# Beta24_to71.net
KiCad netlist of a schematic drawn in EAGLE
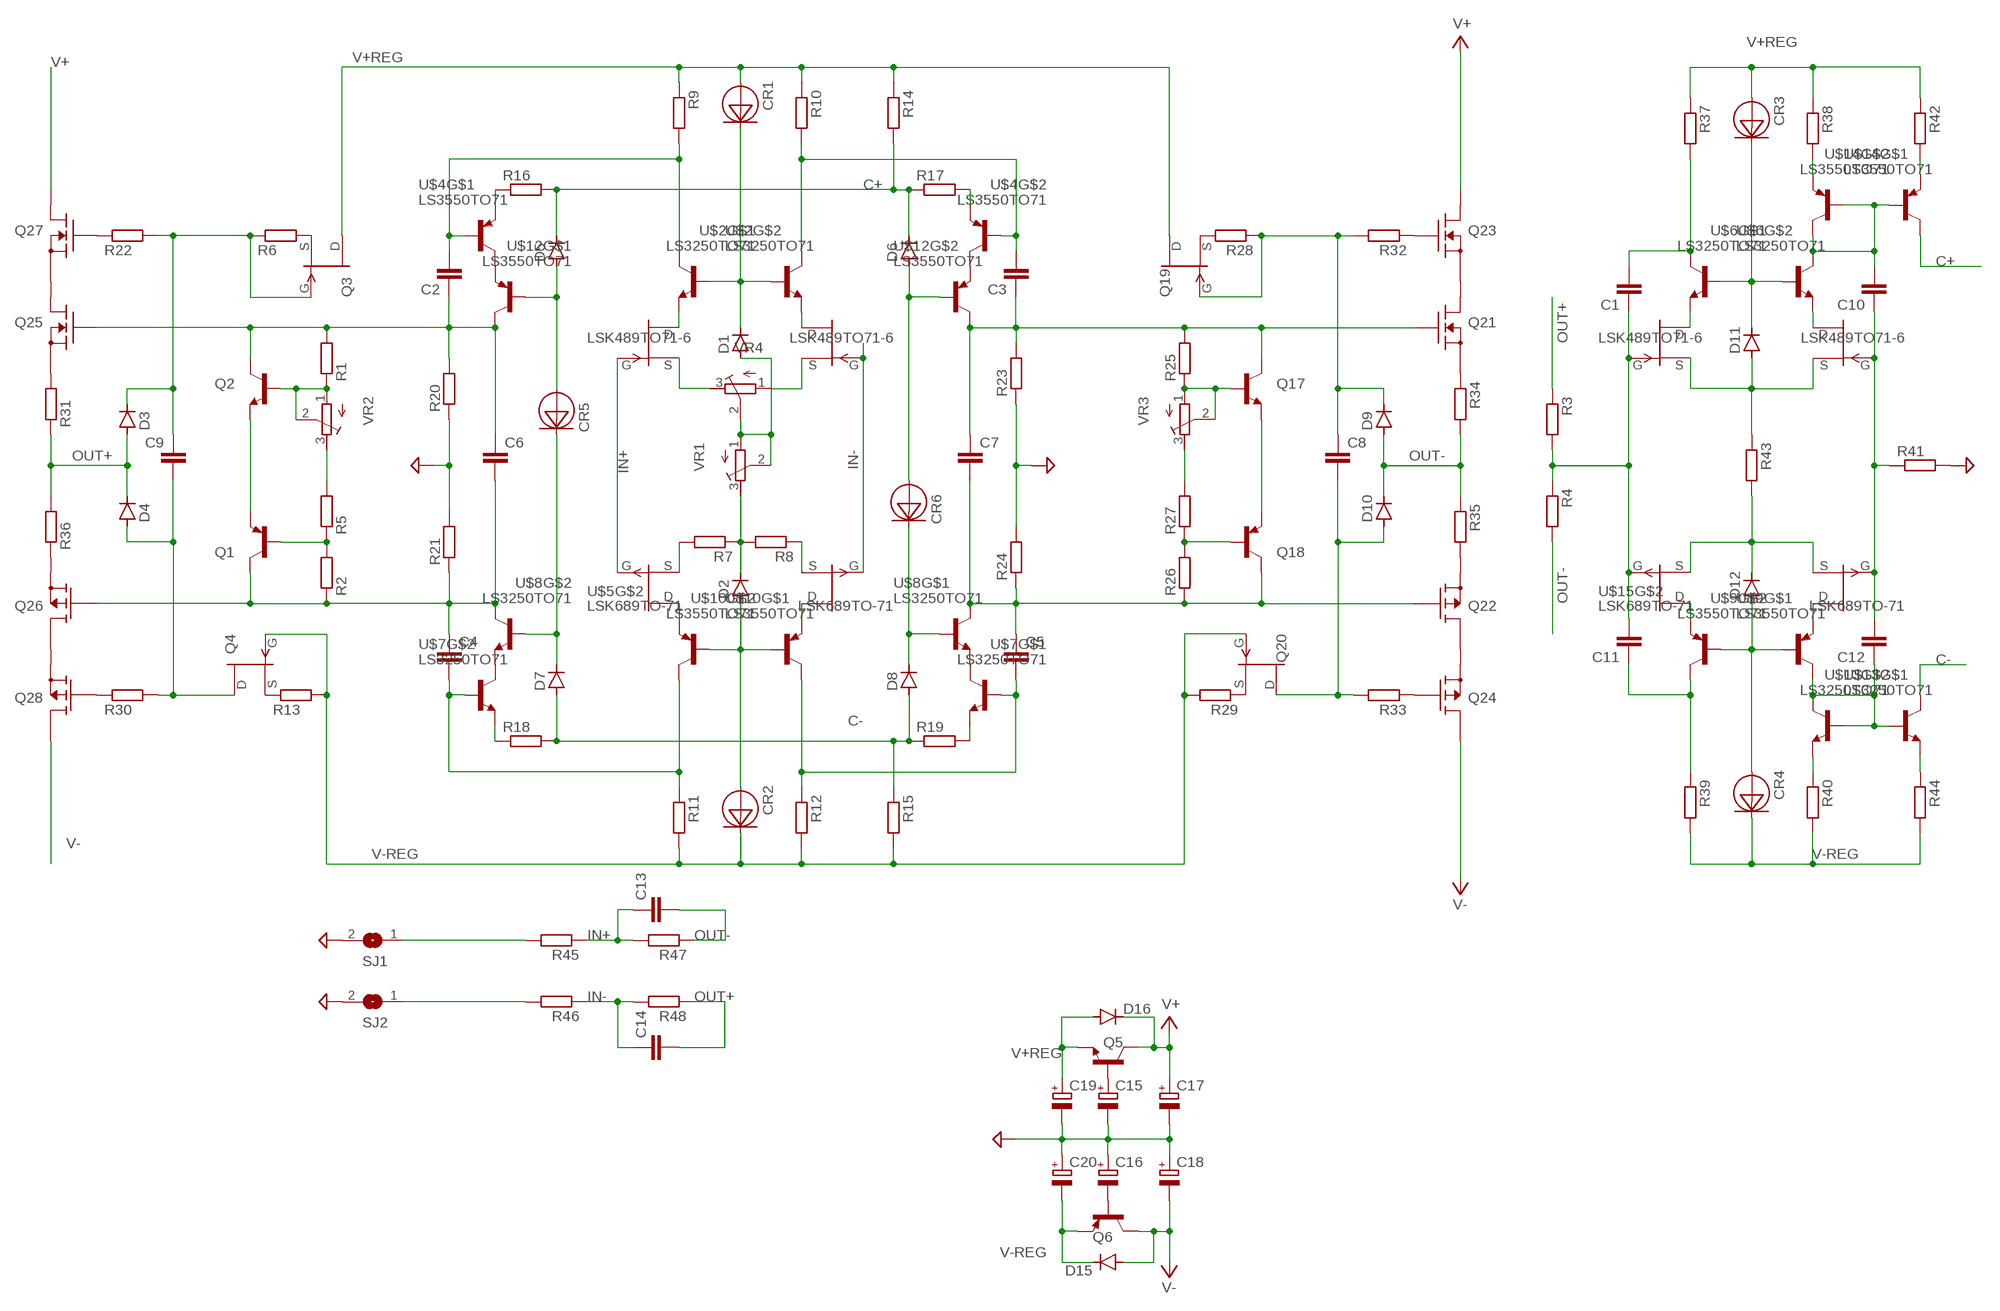
[diagram p0: schematic, sheet 1]

(export (version "E")
  (design (tool "Eeschema 10.0.6"))
  (components
    (comp (ref "C1")
      (value "C-EUC1206")
      (footprint "eagle-import:C1206")
      (libsource (lib "eagle-import") (part "C-EUC1206"))
    )
    (comp (ref "C2")
      (value "C-EUC1206")
      (footprint "eagle-import:C1206")
      (libsource (lib "eagle-import") (part "C-EUC1206"))
    )
    (comp (ref "C3")
      (value "C-EUC1206")
      (footprint "eagle-import:C1206")
      (libsource (lib "eagle-import") (part "C-EUC1206"))
    )
    (comp (ref "C4")
      (value "C-EUC1206")
      (footprint "eagle-import:C1206")
      (libsource (lib "eagle-import") (part "C-EUC1206"))
    )
    (comp (ref "C5")
      (value "C-EUC1206")
      (footprint "eagle-import:C1206")
      (libsource (lib "eagle-import") (part "C-EUC1206"))
    )
    (comp (ref "C6")
      (value "C-EUC1206")
      (footprint "eagle-import:C1206")
      (libsource (lib "eagle-import") (part "C-EUC1206"))
    )
    (comp (ref "C7")
      (value "C-EUC1206")
      (footprint "eagle-import:C1206")
      (libsource (lib "eagle-import") (part "C-EUC1206"))
    )
    (comp (ref "C8")
      (value "C-EUC1206")
      (footprint "eagle-import:C1206")
      (libsource (lib "eagle-import") (part "C-EUC1206"))
    )
    (comp (ref "C9")
      (value "C-EUC1206")
      (footprint "eagle-import:C1206")
      (libsource (lib "eagle-import") (part "C-EUC1206"))
    )
    (comp (ref "C10")
      (value "C-EUC1206")
      (footprint "eagle-import:C1206")
      (libsource (lib "eagle-import") (part "C-EUC1206"))
    )
    (comp (ref "C11")
      (value "C-EUC1206")
      (footprint "eagle-import:C1206")
      (libsource (lib "eagle-import") (part "C-EUC1206"))
    )
    (comp (ref "C12")
      (value "C-EUC1206")
      (footprint "eagle-import:C1206")
      (libsource (lib "eagle-import") (part "C-EUC1206"))
    )
    (comp (ref "C13")
      (value "C-EUC1206")
      (footprint "eagle-import:C1206")
      (libsource (lib "eagle-import") (part "C-EUC1206"))
    )
    (comp (ref "C14")
      (value "C-EUC1206")
      (footprint "eagle-import:C1206")
      (libsource (lib "eagle-import") (part "C-EUC1206"))
    )
    (comp (ref "C15")
      (value "CPOL-EUE5-13")
      (footprint "eagle-import:E5-13")
      (libsource (lib "eagle-import") (part "CPOL-EUE5-13"))
    )
    (comp (ref "C16")
      (value "CPOL-EUE5-13")
      (footprint "eagle-import:E5-13")
      (libsource (lib "eagle-import") (part "CPOL-EUE5-13"))
    )
    (comp (ref "C17")
      (value "CPOL-EUE7.5-18")
      (footprint "eagle-import:E7,5-18")
      (libsource (lib "eagle-import") (part "CPOL-EUE7.5-18"))
    )
    (comp (ref "C18")
      (value "CPOL-EUE7.5-18")
      (footprint "eagle-import:E7,5-18")
      (libsource (lib "eagle-import") (part "CPOL-EUE7.5-18"))
    )
    (comp (ref "C19")
      (value "CPOL-EUE5-13")
      (footprint "eagle-import:E5-13")
      (libsource (lib "eagle-import") (part "CPOL-EUE5-13"))
    )
    (comp (ref "C20")
      (value "CPOL-EUE5-13")
      (footprint "eagle-import:E5-13")
      (libsource (lib "eagle-import") (part "CPOL-EUE5-13"))
    )
    (comp (ref "CR1")
      (value "1N5283")
      (footprint "eagle-import:SMD")
      (libsource (lib "eagle-import") (part "1N5283"))
    )
    (comp (ref "CR2")
      (value "1N5283")
      (footprint "eagle-import:SMD")
      (libsource (lib "eagle-import") (part "1N5283"))
    )
    (comp (ref "CR3")
      (value "1N5283")
      (footprint "eagle-import:SMD")
      (libsource (lib "eagle-import") (part "1N5283"))
    )
    (comp (ref "CR4")
      (value "1N5283")
      (footprint "eagle-import:SMD")
      (libsource (lib "eagle-import") (part "1N5283"))
    )
    (comp (ref "CR5")
      (value "1N5283")
      (footprint "eagle-import:SMD")
      (libsource (lib "eagle-import") (part "1N5283"))
    )
    (comp (ref "CR6")
      (value "1N5283")
      (footprint "eagle-import:SMD")
      (libsource (lib "eagle-import") (part "1N5283"))
    )
    (comp (ref "D1")
      (value "DIODE-SOD80C")
      (footprint "eagle-import:SOD80C")
      (libsource (lib "eagle-import") (part "DIODE-SOD80C"))
    )
    (comp (ref "D2")
      (value "DIODE-SOD80C")
      (footprint "eagle-import:SOD80C")
      (libsource (lib "eagle-import") (part "DIODE-SOD80C"))
    )
    (comp (ref "D3")
      (value "DIODE-SOD80C")
      (footprint "eagle-import:SOD80C")
      (libsource (lib "eagle-import") (part "DIODE-SOD80C"))
    )
    (comp (ref "D4")
      (value "DIODE-SOD80C")
      (footprint "eagle-import:SOD80C")
      (libsource (lib "eagle-import") (part "DIODE-SOD80C"))
    )
    (comp (ref "D5")
      (value "DIODE-SOD80C")
      (footprint "eagle-import:SOD80C")
      (libsource (lib "eagle-import") (part "DIODE-SOD80C"))
    )
    (comp (ref "D6")
      (value "DIODE-SOD80C")
      (footprint "eagle-import:SOD80C")
      (libsource (lib "eagle-import") (part "DIODE-SOD80C"))
    )
    (comp (ref "D7")
      (value "DIODE-SOD80C")
      (footprint "eagle-import:SOD80C")
      (libsource (lib "eagle-import") (part "DIODE-SOD80C"))
    )
    (comp (ref "D8")
      (value "DIODE-SOD80C")
      (footprint "eagle-import:SOD80C")
      (libsource (lib "eagle-import") (part "DIODE-SOD80C"))
    )
    (comp (ref "D9")
      (value "DIODE-SOD80C")
      (footprint "eagle-import:SOD80C")
      (libsource (lib "eagle-import") (part "DIODE-SOD80C"))
    )
    (comp (ref "D10")
      (value "DIODE-SOD80C")
      (footprint "eagle-import:SOD80C")
      (libsource (lib "eagle-import") (part "DIODE-SOD80C"))
    )
    (comp (ref "D11")
      (value "DIODE-SOD80C")
      (footprint "eagle-import:SOD80C")
      (libsource (lib "eagle-import") (part "DIODE-SOD80C"))
    )
    (comp (ref "D12")
      (value "DIODE-SOD80C")
      (footprint "eagle-import:SOD80C")
      (libsource (lib "eagle-import") (part "DIODE-SOD80C"))
    )
    (comp (ref "D15")
      (value "DIODE-SMB")
      (footprint "eagle-import:SMB")
      (libsource (lib "eagle-import") (part "DIODE-SMB"))
    )
    (comp (ref "D16")
      (value "DIODE-SMB")
      (footprint "eagle-import:SMB")
      (libsource (lib "eagle-import") (part "DIODE-SMB"))
    )
    (comp (ref "Q1")
      (value "TRANSISTOR_BC858C-PNP-SOT23-BEC")
      (footprint "eagle-import:TRANSISTOR_SOT23-BEC")
      (libsource (lib "eagle-import") (part "TRANSISTOR_-PNP-SOT23-BECBC858C"))
    )
    (comp (ref "Q2")
      (value "TRANSISTOR_BC850-NPN-SOT23-BEC")
      (footprint "eagle-import:TRANSISTOR_SOT23-BEC")
      (libsource (lib "eagle-import") (part "TRANSISTOR_-NPN-SOT23-BECBC850"))
    )
    (comp (ref "Q3")
      (value "2N4392")
      (footprint "eagle-import:TO18")
      (libsource (lib "eagle-import") (part "2N4392"))
    )
    (comp (ref "Q4")
      (value "2N4392")
      (footprint "eagle-import:TO18")
      (libsource (lib "eagle-import") (part "2N4392"))
    )
    (comp (ref "Q5")
      (value "TRANSISTOR_MMBTA42LT1-NPN-SOT23-BEC")
      (footprint "eagle-import:TRANSISTOR_SOT23-BEC")
      (libsource (lib "eagle-import") (part "TRANSISTOR_-NPN-SOT23-BECMMBTA42LT1"))
    )
    (comp (ref "Q6")
      (value "TRANSISTOR_MMBTA92LT1-PNP-SOT23-BEC")
      (footprint "eagle-import:TRANSISTOR_SOT23-BEC")
      (libsource (lib "eagle-import") (part "TRANSISTOR_-PNP-SOT23-BECMMBTA92LT1"))
    )
    (comp (ref "Q17")
      (value "TRANSISTOR_BC850-NPN-SOT23-BEC")
      (footprint "eagle-import:TRANSISTOR_SOT23-BEC")
      (libsource (lib "eagle-import") (part "TRANSISTOR_-NPN-SOT23-BECBC850"))
    )
    (comp (ref "Q18")
      (value "TRANSISTOR_BC858C-PNP-SOT23-BEC")
      (footprint "eagle-import:TRANSISTOR_SOT23-BEC")
      (libsource (lib "eagle-import") (part "TRANSISTOR_-PNP-SOT23-BECBC858C"))
    )
    (comp (ref "Q19")
      (value "2N4392")
      (footprint "eagle-import:TO18")
      (libsource (lib "eagle-import") (part "2N4392"))
    )
    (comp (ref "Q20")
      (value "2N4392")
      (footprint "eagle-import:TO18")
      (libsource (lib "eagle-import") (part "2N4392"))
    )
    (comp (ref "Q21")
      (value "IRFZ24N")
      (footprint "eagle-import:TO220V")
      (libsource (lib "eagle-import") (part "IRFZ24N"))
    )
    (comp (ref "Q22")
      (value "IRFZ34N")
      (footprint "eagle-import:TO220V")
      (libsource (lib "eagle-import") (part "IRFZ34N"))
    )
    (comp (ref "Q23")
      (value "IRFZ24N")
      (footprint "eagle-import:TO220V")
      (libsource (lib "eagle-import") (part "IRFZ24N"))
    )
    (comp (ref "Q24")
      (value "IRFZ34N")
      (footprint "eagle-import:TO220V")
      (libsource (lib "eagle-import") (part "IRFZ34N"))
    )
    (comp (ref "Q25")
      (value "IRFZ24N")
      (footprint "eagle-import:TO220V")
      (libsource (lib "eagle-import") (part "IRFZ24N"))
    )
    (comp (ref "Q26")
      (value "IRFZ34N")
      (footprint "eagle-import:TO220V")
      (libsource (lib "eagle-import") (part "IRFZ34N"))
    )
    (comp (ref "Q27")
      (value "IRFZ24N")
      (footprint "eagle-import:TO220V")
      (libsource (lib "eagle-import") (part "IRFZ24N"))
    )
    (comp (ref "Q28")
      (value "IRFZ34N")
      (footprint "eagle-import:TO220V")
      (libsource (lib "eagle-import") (part "IRFZ34N"))
    )
    (comp (ref "R1")
      (value "R-EU_MELF0204W")
      (footprint "eagle-import:MINI_MELF-0204W")
      (libsource (lib "eagle-import") (part "R-EU_MELF0204W"))
    )
    (comp (ref "R2")
      (value "R-EU_MELF0204W")
      (footprint "eagle-import:MINI_MELF-0204W")
      (libsource (lib "eagle-import") (part "R-EU_MELF0204W"))
    )
    (comp (ref "R3")
      (value "R-EU_MELF0204W")
      (footprint "eagle-import:MINI_MELF-0204W")
      (libsource (lib "eagle-import") (part "R-EU_MELF0204W"))
    )
    (comp (ref "R4")
      (value "R-EU_MELF0204W")
      (footprint "eagle-import:MINI_MELF-0204W")
      (libsource (lib "eagle-import") (part "R-EU_MELF0204W"))
    )
    (comp (ref "R5")
      (value "R-EU_MELF0204W")
      (footprint "eagle-import:MINI_MELF-0204W")
      (libsource (lib "eagle-import") (part "R-EU_MELF0204W"))
    )
    (comp (ref "R6")
      (value "R-EU_MELF0204W")
      (footprint "eagle-import:MINI_MELF-0204W")
      (libsource (lib "eagle-import") (part "R-EU_MELF0204W"))
    )
    (comp (ref "R7")
      (value "R-EU_MELF0204W")
      (footprint "eagle-import:MINI_MELF-0204W")
      (libsource (lib "eagle-import") (part "R-EU_MELF0204W"))
    )
    (comp (ref "R8")
      (value "R-EU_MELF0204W")
      (footprint "eagle-import:MINI_MELF-0204W")
      (libsource (lib "eagle-import") (part "R-EU_MELF0204W"))
    )
    (comp (ref "R9")
      (value "R-EU_MELF0204W")
      (footprint "eagle-import:MINI_MELF-0204W")
      (libsource (lib "eagle-import") (part "R-EU_MELF0204W"))
    )
    (comp (ref "R10")
      (value "R-EU_MELF0204W")
      (footprint "eagle-import:MINI_MELF-0204W")
      (libsource (lib "eagle-import") (part "R-EU_MELF0204W"))
    )
    (comp (ref "R11")
      (value "R-EU_MELF0204W")
      (footprint "eagle-import:MINI_MELF-0204W")
      (libsource (lib "eagle-import") (part "R-EU_MELF0204W"))
    )
    (comp (ref "R12")
      (value "R-EU_MELF0204W")
      (footprint "eagle-import:MINI_MELF-0204W")
      (libsource (lib "eagle-import") (part "R-EU_MELF0204W"))
    )
    (comp (ref "R13")
      (value "R-EU_MELF0204W")
      (footprint "eagle-import:MINI_MELF-0204W")
      (libsource (lib "eagle-import") (part "R-EU_MELF0204W"))
    )
    (comp (ref "R14")
      (value "R-EU_MELF0204W")
      (footprint "eagle-import:MINI_MELF-0204W")
      (libsource (lib "eagle-import") (part "R-EU_MELF0204W"))
    )
    (comp (ref "R15")
      (value "R-EU_MELF0204W")
      (footprint "eagle-import:MINI_MELF-0204W")
      (libsource (lib "eagle-import") (part "R-EU_MELF0204W"))
    )
    (comp (ref "R16")
      (value "R-EU_MELF0204W")
      (footprint "eagle-import:MINI_MELF-0204W")
      (libsource (lib "eagle-import") (part "R-EU_MELF0204W"))
    )
    (comp (ref "R17")
      (value "R-EU_MELF0204W")
      (footprint "eagle-import:MINI_MELF-0204W")
      (libsource (lib "eagle-import") (part "R-EU_MELF0204W"))
    )
    (comp (ref "R18")
      (value "R-EU_MELF0204W")
      (footprint "eagle-import:MINI_MELF-0204W")
      (libsource (lib "eagle-import") (part "R-EU_MELF0204W"))
    )
    (comp (ref "R19")
      (value "R-EU_MELF0204W")
      (footprint "eagle-import:MINI_MELF-0204W")
      (libsource (lib "eagle-import") (part "R-EU_MELF0204W"))
    )
    (comp (ref "R20")
      (value "R-EU_MELF0204W")
      (footprint "eagle-import:MINI_MELF-0204W")
      (libsource (lib "eagle-import") (part "R-EU_MELF0204W"))
    )
    (comp (ref "R21")
      (value "R-EU_MELF0204W")
      (footprint "eagle-import:MINI_MELF-0204W")
      (libsource (lib "eagle-import") (part "R-EU_MELF0204W"))
    )
    (comp (ref "R22")
      (value "R-EU_MELF0204W")
      (footprint "eagle-import:MINI_MELF-0204W")
      (libsource (lib "eagle-import") (part "R-EU_MELF0204W"))
    )
    (comp (ref "R23")
      (value "R-EU_MELF0204W")
      (footprint "eagle-import:MINI_MELF-0204W")
      (libsource (lib "eagle-import") (part "R-EU_MELF0204W"))
    )
    (comp (ref "R24")
      (value "R-EU_MELF0204W")
      (footprint "eagle-import:MINI_MELF-0204W")
      (libsource (lib "eagle-import") (part "R-EU_MELF0204W"))
    )
    (comp (ref "R25")
      (value "R-EU_MELF0204W")
      (footprint "eagle-import:MINI_MELF-0204W")
      (libsource (lib "eagle-import") (part "R-EU_MELF0204W"))
    )
    (comp (ref "R26")
      (value "R-EU_MELF0204W")
      (footprint "eagle-import:MINI_MELF-0204W")
      (libsource (lib "eagle-import") (part "R-EU_MELF0204W"))
    )
    (comp (ref "R27")
      (value "R-EU_MELF0204W")
      (footprint "eagle-import:MINI_MELF-0204W")
      (libsource (lib "eagle-import") (part "R-EU_MELF0204W"))
    )
    (comp (ref "R28")
      (value "R-EU_MELF0204W")
      (footprint "eagle-import:MINI_MELF-0204W")
      (libsource (lib "eagle-import") (part "R-EU_MELF0204W"))
    )
    (comp (ref "R29")
      (value "R-EU_MELF0204W")
      (footprint "eagle-import:MINI_MELF-0204W")
      (libsource (lib "eagle-import") (part "R-EU_MELF0204W"))
    )
    (comp (ref "R30")
      (value "R-EU_MELF0204W")
      (footprint "eagle-import:MINI_MELF-0204W")
      (libsource (lib "eagle-import") (part "R-EU_MELF0204W"))
    )
    (comp (ref "R31")
      (value "R-EU_TO220")
      (footprint "eagle-import:TO220-2")
      (libsource (lib "eagle-import") (part "R-EU_TO220"))
    )
    (comp (ref "R32")
      (value "R-EU_MELF0204W")
      (footprint "eagle-import:MINI_MELF-0204W")
      (libsource (lib "eagle-import") (part "R-EU_MELF0204W"))
    )
    (comp (ref "R33")
      (value "R-EU_MELF0204W")
      (footprint "eagle-import:MINI_MELF-0204W")
      (libsource (lib "eagle-import") (part "R-EU_MELF0204W"))
    )
    (comp (ref "R34")
      (value "R-EU_TO220")
      (footprint "eagle-import:TO220-2")
      (libsource (lib "eagle-import") (part "R-EU_TO220"))
    )
    (comp (ref "R35")
      (value "R-EU_TO220")
      (footprint "eagle-import:TO220-2")
      (libsource (lib "eagle-import") (part "R-EU_TO220"))
    )
    (comp (ref "R36")
      (value "R-EU_TO220")
      (footprint "eagle-import:TO220-2")
      (libsource (lib "eagle-import") (part "R-EU_TO220"))
    )
    (comp (ref "R37")
      (value "R-EU_MELF0204W")
      (footprint "eagle-import:MINI_MELF-0204W")
      (libsource (lib "eagle-import") (part "R-EU_MELF0204W"))
    )
    (comp (ref "R38")
      (value "R-EU_MELF0204W")
      (footprint "eagle-import:MINI_MELF-0204W")
      (libsource (lib "eagle-import") (part "R-EU_MELF0204W"))
    )
    (comp (ref "R39")
      (value "R-EU_MELF0204W")
      (footprint "eagle-import:MINI_MELF-0204W")
      (libsource (lib "eagle-import") (part "R-EU_MELF0204W"))
    )
    (comp (ref "R40")
      (value "R-EU_MELF0204W")
      (footprint "eagle-import:MINI_MELF-0204W")
      (libsource (lib "eagle-import") (part "R-EU_MELF0204W"))
    )
    (comp (ref "R41")
      (value "R-EU_MELF0204W")
      (footprint "eagle-import:MINI_MELF-0204W")
      (libsource (lib "eagle-import") (part "R-EU_MELF0204W"))
    )
    (comp (ref "R42")
      (value "R-EU_MELF0204W")
      (footprint "eagle-import:MINI_MELF-0204W")
      (libsource (lib "eagle-import") (part "R-EU_MELF0204W"))
    )
    (comp (ref "R43")
      (value "R-EU_MELF0204W")
      (footprint "eagle-import:MINI_MELF-0204W")
      (libsource (lib "eagle-import") (part "R-EU_MELF0204W"))
    )
    (comp (ref "R44")
      (value "R-EU_MELF0204W")
      (footprint "eagle-import:MINI_MELF-0204W")
      (libsource (lib "eagle-import") (part "R-EU_MELF0204W"))
    )
    (comp (ref "R45")
      (value "R-EU_MELF0204W")
      (footprint "eagle-import:MINI_MELF-0204W")
      (libsource (lib "eagle-import") (part "R-EU_MELF0204W"))
    )
    (comp (ref "R46")
      (value "R-EU_MELF0204W")
      (footprint "eagle-import:MINI_MELF-0204W")
      (libsource (lib "eagle-import") (part "R-EU_MELF0204W"))
    )
    (comp (ref "R47")
      (value "R-EU_MELF0204W")
      (footprint "eagle-import:MINI_MELF-0204W")
      (libsource (lib "eagle-import") (part "R-EU_MELF0204W"))
    )
    (comp (ref "R48")
      (value "R-EU_MELF0204W")
      (footprint "eagle-import:MINI_MELF-0204W")
      (libsource (lib "eagle-import") (part "R-EU_MELF0204W"))
    )
    (comp (ref "SJ1") (value "SJ") (footprint "eagle-import:SJ") (libsource (lib "eagle-import") (part "SJ")))
    (comp (ref "SJ2") (value "SJ") (footprint "eagle-import:SJ") (libsource (lib "eagle-import") (part "SJ")))
    (comp (ref "U$1")
      (value "LSK489TO71-6")
      (footprint "eagle-import:TO71-6")
      (libsource (lib "eagle-import") (part "LSK489TO71-6"))
    )
    (comp (ref "U$2")
      (value "LS3250TO71")
      (footprint "eagle-import:TO71-6")
      (libsource (lib "eagle-import") (part "LS3250TO71"))
    )
    (comp (ref "U$3")
      (value "LSK489TO71-6")
      (footprint "eagle-import:TO71-6")
      (libsource (lib "eagle-import") (part "LSK489TO71-6"))
    )
    (comp (ref "U$4")
      (value "LS3550TO71")
      (footprint "eagle-import:TO71-6")
      (libsource (lib "eagle-import") (part "LS3550TO71"))
    )
    (comp (ref "U$5")
      (value "LSK689TO-71")
      (footprint "eagle-import:TO71-6")
      (libsource (lib "eagle-import") (part "LSK689TO-71"))
    )
    (comp (ref "U$6")
      (value "LS3250TO71")
      (footprint "eagle-import:TO71-6")
      (libsource (lib "eagle-import") (part "LS3250TO71"))
    )
    (comp (ref "U$7")
      (value "LS3250TO71")
      (footprint "eagle-import:TO71-6")
      (libsource (lib "eagle-import") (part "LS3250TO71"))
    )
    (comp (ref "U$8")
      (value "LS3250TO71")
      (footprint "eagle-import:TO71-6")
      (libsource (lib "eagle-import") (part "LS3250TO71"))
    )
    (comp (ref "U$9")
      (value "LS3550TO71")
      (footprint "eagle-import:TO71-6")
      (libsource (lib "eagle-import") (part "LS3550TO71"))
    )
    (comp (ref "U$10")
      (value "LS3550TO71")
      (footprint "eagle-import:TO71-6")
      (libsource (lib "eagle-import") (part "LS3550TO71"))
    )
    (comp (ref "U$12")
      (value "LS3550TO71")
      (footprint "eagle-import:TO71-6")
      (libsource (lib "eagle-import") (part "LS3550TO71"))
    )
    (comp (ref "U$13")
      (value "LS3250TO71")
      (footprint "eagle-import:TO71-6")
      (libsource (lib "eagle-import") (part "LS3250TO71"))
    )
    (comp (ref "U$14")
      (value "LS3550TO71")
      (footprint "eagle-import:TO71-6")
      (libsource (lib "eagle-import") (part "LS3550TO71"))
    )
    (comp (ref "U$15")
      (value "LSK689TO-71")
      (footprint "eagle-import:TO71-6")
      (libsource (lib "eagle-import") (part "LSK689TO-71"))
    )
    (comp (ref "VR1")
      (value "R-TRIMM3296W")
      (footprint "eagle-import:RTRIM3296W")
      (libsource (lib "eagle-import") (part "R-TRIMM3296W"))
    )
    (comp (ref "VR2")
      (value "R-TRIMM3296W")
      (footprint "eagle-import:RTRIM3296W")
      (libsource (lib "eagle-import") (part "R-TRIMM3296W"))
    )
    (comp (ref "VR3")
      (value "R-TRIMM3296W")
      (footprint "eagle-import:RTRIM3296W")
      (libsource (lib "eagle-import") (part "R-TRIMM3296W"))
    )
    (comp (ref "VR4")
      (value "R-TRIMM3296W")
      (footprint "eagle-import:RTRIM3296W")
      (libsource (lib "eagle-import") (part "R-TRIMM3296W"))
    )
  )
  (nets
    (net (code "1") (name "/C+") (class "Default")
      (node (ref "D5") (pin "C") (pinfunction "C_C") (pintype "passive"))
      (node (ref "D6") (pin "C") (pinfunction "C_C") (pintype "passive"))
      (node (ref "R14") (pin "2") (pinfunction "2_2") (pintype "passive"))
      (node (ref "R16") (pin "2") (pinfunction "2_2") (pintype "passive"))
      (node (ref "R17") (pin "1") (pinfunction "1_1") (pintype "passive"))
      (node (ref "U$14") (pin "1") (pinfunction "C_1") (pintype "passive"))
    )
    (net (code "2") (name "/C-") (class "Default")
      (node (ref "D7") (pin "A") (pinfunction "A_A") (pintype "passive"))
      (node (ref "D8") (pin "A") (pinfunction "A_A") (pintype "passive"))
      (node (ref "R15") (pin "1") (pinfunction "1_1") (pintype "passive"))
      (node (ref "R18") (pin "2") (pinfunction "2_2") (pintype "passive"))
      (node (ref "R19") (pin "1") (pinfunction "1_1") (pintype "passive"))
      (node (ref "U$13") (pin "1") (pinfunction "C_1") (pintype "passive"))
    )
    (net (code "3") (name "/IN+") (class "Default")
      (node (ref "C13") (pin "1") (pinfunction "1_1") (pintype "passive"))
      (node (ref "R45") (pin "1") (pinfunction "1_1") (pintype "passive"))
      (node (ref "R47") (pin "2") (pinfunction "2_2") (pintype "passive"))
      (node (ref "U$1") (pin "3") (pinfunction "G_3") (pintype "passive"))
      (node (ref "U$5") (pin "7") (pinfunction "G_7") (pintype "passive"))
    )
    (net (code "4") (name "/IN-") (class "Default")
      (node (ref "C14") (pin "1") (pinfunction "1_1") (pintype "passive"))
      (node (ref "R46") (pin "1") (pinfunction "1_1") (pintype "passive"))
      (node (ref "R48") (pin "2") (pinfunction "2_2") (pintype "passive"))
      (node (ref "U$1") (pin "7") (pinfunction "G_7") (pintype "passive"))
      (node (ref "U$5") (pin "3") (pinfunction "G_3") (pintype "passive"))
    )
    (net (code "5") (name "/OUT+") (class "Default")
      (node (ref "C14") (pin "2") (pinfunction "2_2") (pintype "passive"))
      (node (ref "D3") (pin "A") (pinfunction "A_A") (pintype "passive"))
      (node (ref "D4") (pin "C") (pinfunction "C_C") (pintype "passive"))
      (node (ref "R3") (pin "1") (pinfunction "1_1") (pintype "passive"))
      (node (ref "R31") (pin "1") (pinfunction "1_1") (pintype "passive"))
      (node (ref "R36") (pin "2") (pinfunction "2_2") (pintype "passive"))
      (node (ref "R48") (pin "1") (pinfunction "1_1") (pintype "passive"))
    )
    (net (code "6") (name "/OUT-") (class "Default")
      (node (ref "C13") (pin "2") (pinfunction "2_2") (pintype "passive"))
      (node (ref "D10") (pin "C") (pinfunction "C_C") (pintype "passive"))
      (node (ref "D9") (pin "A") (pinfunction "A_A") (pintype "passive"))
      (node (ref "R34") (pin "2") (pinfunction "2_2") (pintype "passive"))
      (node (ref "R35") (pin "1") (pinfunction "1_1") (pintype "passive"))
      (node (ref "R4") (pin "2") (pinfunction "2_2") (pintype "passive"))
      (node (ref "R47") (pin "1") (pinfunction "1_1") (pintype "passive"))
    )
    (net (code "7") (name "/V+REG") (class "Default")
      (node (ref "C19") (pin "+") (pinfunction "+_+") (pintype "passive"))
      (node (ref "CR1") (pin "ANODE") (pinfunction "ANODE_ANODE") (pintype "passive"))
      (node (ref "CR3") (pin "ANODE") (pinfunction "ANODE_ANODE") (pintype "passive"))
      (node (ref "D16") (pin "A") (pinfunction "A_A") (pintype "passive"))
      (node (ref "Q19") (pin "2") (pinfunction "D_2") (pintype "passive"))
      (node (ref "Q3") (pin "2") (pinfunction "D_2") (pintype "passive"))
      (node (ref "Q5") (pin "E") (pinfunction "E_E") (pintype "passive"))
      (node (ref "R10") (pin "1") (pinfunction "1_1") (pintype "passive"))
      (node (ref "R14") (pin "1") (pinfunction "1_1") (pintype "passive"))
      (node (ref "R37") (pin "1") (pinfunction "1_1") (pintype "passive"))
      (node (ref "R38") (pin "1") (pinfunction "1_1") (pintype "passive"))
      (node (ref "R42") (pin "1") (pinfunction "1_1") (pintype "passive"))
      (node (ref "R9") (pin "1") (pinfunction "1_1") (pintype "passive"))
    )
    (net (code "8") (name "/V-REG") (class "Default")
      (node (ref "C20") (pin "-") (pinfunction "-_-") (pintype "passive"))
      (node (ref "CR2") (pin "CATHODE") (pinfunction "CATHODE_CATHODE") (pintype "passive"))
      (node (ref "CR4") (pin "CATHODE") (pinfunction "CATHODE_CATHODE") (pintype "passive"))
      (node (ref "D15") (pin "C") (pinfunction "C_C") (pintype "passive"))
      (node (ref "Q20") (pin "3") (pinfunction "G_3") (pintype "passive"))
      (node (ref "Q4") (pin "3") (pinfunction "G_3") (pintype "passive"))
      (node (ref "Q6") (pin "E") (pinfunction "E_E") (pintype "passive"))
      (node (ref "R11") (pin "2") (pinfunction "2_2") (pintype "passive"))
      (node (ref "R12") (pin "2") (pinfunction "2_2") (pintype "passive"))
      (node (ref "R13") (pin "2") (pinfunction "2_2") (pintype "passive"))
      (node (ref "R15") (pin "2") (pinfunction "2_2") (pintype "passive"))
      (node (ref "R29") (pin "2") (pinfunction "2_2") (pintype "passive"))
      (node (ref "R39") (pin "2") (pinfunction "2_2") (pintype "passive"))
      (node (ref "R40") (pin "2") (pinfunction "2_2") (pintype "passive"))
      (node (ref "R44") (pin "2") (pinfunction "2_2") (pintype "passive"))
    )
    (net (code "9") (name "GND") (class "Default")
      (node (ref "C15") (pin "-") (pinfunction "-_-") (pintype "passive"))
      (node (ref "C16") (pin "+") (pinfunction "+_+") (pintype "passive"))
      (node (ref "C17") (pin "-") (pinfunction "-_-") (pintype "passive"))
      (node (ref "C18") (pin "+") (pinfunction "+_+") (pintype "passive"))
      (node (ref "C19") (pin "-") (pinfunction "-_-") (pintype "passive"))
      (node (ref "C20") (pin "+") (pinfunction "+_+") (pintype "passive"))
      (node (ref "R20") (pin "1") (pinfunction "1_1") (pintype "passive"))
      (node (ref "R21") (pin "2") (pinfunction "2_2") (pintype "passive"))
      (node (ref "R23") (pin "1") (pinfunction "1_1") (pintype "passive"))
      (node (ref "R24") (pin "2") (pinfunction "2_2") (pintype "passive"))
      (node (ref "R41") (pin "2") (pinfunction "2_2") (pintype "passive"))
      (node (ref "SJ1") (pin "2") (pinfunction "2_2") (pintype "passive"))
      (node (ref "SJ2") (pin "2") (pinfunction "2_2") (pintype "passive"))
    )
    (net (code "10") (name "Net-(C15-Pad+)") (class "Default")
      (node (ref "C15") (pin "+") (pinfunction "+_+") (pintype "passive"))
      (node (ref "Q5") (pin "B") (pinfunction "B_B") (pintype "passive"))
    )
    (net (code "11") (name "Net-(C16-Pad-)") (class "Default")
      (node (ref "C16") (pin "-") (pinfunction "-_-") (pintype "passive"))
      (node (ref "Q6") (pin "B") (pinfunction "B_B") (pintype "passive"))
    )
    (net (code "12") (name "Net-(Q1-PadB)") (class "Default")
      (node (ref "Q1") (pin "B") (pinfunction "B_B") (pintype "passive"))
      (node (ref "R2") (pin "2") (pinfunction "2_2") (pintype "passive"))
      (node (ref "R5") (pin "1") (pinfunction "1_1") (pintype "passive"))
    )
    (net (code "13") (name "Net-(Q1-PadE)") (class "Default")
      (node (ref "Q1") (pin "E") (pinfunction "E_E") (pintype "passive"))
      (node (ref "Q2") (pin "E") (pinfunction "E_E") (pintype "passive"))
    )
    (net (code "14") (name "Net-(Q3-G)") (class "Default")
      (node (ref "C9") (pin "1") (pinfunction "1_1") (pintype "passive"))
      (node (ref "D3") (pin "C") (pinfunction "C_C") (pintype "passive"))
      (node (ref "Q3") (pin "3") (pinfunction "G_3") (pintype "passive"))
      (node (ref "R22") (pin "2") (pinfunction "2_2") (pintype "passive"))
      (node (ref "R6") (pin "1") (pinfunction "1_1") (pintype "passive"))
    )
    (net (code "15") (name "Net-(Q3-S)") (class "Default")
      (node (ref "Q3") (pin "1") (pinfunction "S_1") (pintype "passive"))
      (node (ref "R6") (pin "2") (pinfunction "2_2") (pintype "passive"))
    )
    (net (code "16") (name "Net-(Q4-D)") (class "Default")
      (node (ref "C9") (pin "2") (pinfunction "2_2") (pintype "passive"))
      (node (ref "D4") (pin "A") (pinfunction "A_A") (pintype "passive"))
      (node (ref "Q4") (pin "2") (pinfunction "D_2") (pintype "passive"))
      (node (ref "R30") (pin "2") (pinfunction "2_2") (pintype "passive"))
    )
    (net (code "17") (name "Net-(Q4-S)") (class "Default")
      (node (ref "Q4") (pin "1") (pinfunction "S_1") (pintype "passive"))
      (node (ref "R13") (pin "1") (pinfunction "1_1") (pintype "passive"))
    )
    (net (code "18") (name "Net-(Q17-PadE)") (class "Default")
      (node (ref "Q17") (pin "E") (pinfunction "E_E") (pintype "passive"))
      (node (ref "Q18") (pin "E") (pinfunction "E_E") (pintype "passive"))
    )
    (net (code "19") (name "Net-(Q18-PadB)") (class "Default")
      (node (ref "Q18") (pin "B") (pinfunction "B_B") (pintype "passive"))
      (node (ref "R26") (pin "2") (pinfunction "2_2") (pintype "passive"))
      (node (ref "R27") (pin "1") (pinfunction "1_1") (pintype "passive"))
    )
    (net (code "20") (name "Net-(Q19-G)") (class "Default")
      (node (ref "C8") (pin "1") (pinfunction "1_1") (pintype "passive"))
      (node (ref "D9") (pin "C") (pinfunction "C_C") (pintype "passive"))
      (node (ref "Q19") (pin "3") (pinfunction "G_3") (pintype "passive"))
      (node (ref "R28") (pin "1") (pinfunction "1_1") (pintype "passive"))
      (node (ref "R32") (pin "2") (pinfunction "2_2") (pintype "passive"))
    )
    (net (code "21") (name "Net-(Q19-S)") (class "Default")
      (node (ref "Q19") (pin "1") (pinfunction "S_1") (pintype "passive"))
      (node (ref "R28") (pin "2") (pinfunction "2_2") (pintype "passive"))
    )
    (net (code "22") (name "Net-(Q20-D)") (class "Default")
      (node (ref "C8") (pin "2") (pinfunction "2_2") (pintype "passive"))
      (node (ref "D10") (pin "A") (pinfunction "A_A") (pintype "passive"))
      (node (ref "Q20") (pin "2") (pinfunction "D_2") (pintype "passive"))
      (node (ref "R33") (pin "2") (pinfunction "2_2") (pintype "passive"))
    )
    (net (code "23") (name "Net-(Q20-S)") (class "Default")
      (node (ref "Q20") (pin "1") (pinfunction "S_1") (pintype "passive"))
      (node (ref "R29") (pin "1") (pinfunction "1_1") (pintype "passive"))
    )
    (net (code "24") (name "Net-(Q21-D)") (class "Default")
      (node (ref "Q21") (pin "2") (pinfunction "D_2") (pintype "passive"))
      (node (ref "Q23") (pin "3") (pinfunction "S_3") (pintype "passive"))
    )
    (net (code "25") (name "Net-(Q21-G)") (class "Default")
      (node (ref "C3") (pin "1") (pinfunction "1_1") (pintype "passive"))
      (node (ref "C7") (pin "1") (pinfunction "1_1") (pintype "passive"))
      (node (ref "Q17") (pin "C") (pinfunction "C_C") (pintype "passive"))
      (node (ref "Q21") (pin "1") (pinfunction "G_1") (pintype "passive"))
      (node (ref "R23") (pin "2") (pinfunction "2_2") (pintype "passive"))
      (node (ref "R25") (pin "2") (pinfunction "2_2") (pintype "passive"))
      (node (ref "U$12") (pin "7") (pinfunction "C_7") (pintype "passive"))
    )
    (net (code "26") (name "Net-(Q21-S)") (class "Default")
      (node (ref "Q21") (pin "3") (pinfunction "S_3") (pintype "passive"))
      (node (ref "R34") (pin "1") (pinfunction "1_1") (pintype "passive"))
    )
    (net (code "27") (name "Net-(Q22-D)") (class "Default")
      (node (ref "Q22") (pin "2") (pinfunction "D_2") (pintype "passive"))
      (node (ref "Q24") (pin "3") (pinfunction "S_3") (pintype "passive"))
    )
    (net (code "28") (name "Net-(Q22-G)") (class "Default")
      (node (ref "C5") (pin "1") (pinfunction "1_1") (pintype "passive"))
      (node (ref "C7") (pin "2") (pinfunction "2_2") (pintype "passive"))
      (node (ref "Q18") (pin "C") (pinfunction "C_C") (pintype "passive"))
      (node (ref "Q22") (pin "1") (pinfunction "G_1") (pintype "passive"))
      (node (ref "R24") (pin "1") (pinfunction "1_1") (pintype "passive"))
      (node (ref "R26") (pin "1") (pinfunction "1_1") (pintype "passive"))
      (node (ref "U$8") (pin "1") (pinfunction "C_1") (pintype "passive"))
    )
    (net (code "29") (name "Net-(Q22-S)") (class "Default")
      (node (ref "Q22") (pin "3") (pinfunction "S_3") (pintype "passive"))
      (node (ref "R35") (pin "2") (pinfunction "2_2") (pintype "passive"))
    )
    (net (code "30") (name "Net-(Q23-G)") (class "Default")
      (node (ref "Q23") (pin "1") (pinfunction "G_1") (pintype "passive"))
      (node (ref "R32") (pin "1") (pinfunction "1_1") (pintype "passive"))
    )
    (net (code "31") (name "Net-(Q24-G)") (class "Default")
      (node (ref "Q24") (pin "1") (pinfunction "G_1") (pintype "passive"))
      (node (ref "R33") (pin "1") (pinfunction "1_1") (pintype "passive"))
    )
    (net (code "32") (name "Net-(Q25-D)") (class "Default")
      (node (ref "Q25") (pin "2") (pinfunction "D_2") (pintype "passive"))
      (node (ref "Q27") (pin "3") (pinfunction "S_3") (pintype "passive"))
    )
    (net (code "33") (name "Net-(Q25-G)") (class "Default")
      (node (ref "C2") (pin "1") (pinfunction "1_1") (pintype "passive"))
      (node (ref "C6") (pin "1") (pinfunction "1_1") (pintype "passive"))
      (node (ref "Q2") (pin "C") (pinfunction "C_C") (pintype "passive"))
      (node (ref "Q25") (pin "1") (pinfunction "G_1") (pintype "passive"))
      (node (ref "R1") (pin "2") (pinfunction "2_2") (pintype "passive"))
      (node (ref "R20") (pin "2") (pinfunction "2_2") (pintype "passive"))
      (node (ref "U$12") (pin "1") (pinfunction "C_1") (pintype "passive"))
    )
    (net (code "34") (name "Net-(Q25-S)") (class "Default")
      (node (ref "Q25") (pin "3") (pinfunction "S_3") (pintype "passive"))
      (node (ref "R31") (pin "2") (pinfunction "2_2") (pintype "passive"))
    )
    (net (code "35") (name "Net-(Q26-D)") (class "Default")
      (node (ref "Q26") (pin "2") (pinfunction "D_2") (pintype "passive"))
      (node (ref "Q28") (pin "3") (pinfunction "S_3") (pintype "passive"))
    )
    (net (code "36") (name "Net-(Q26-G)") (class "Default")
      (node (ref "C4") (pin "1") (pinfunction "1_1") (pintype "passive"))
      (node (ref "C6") (pin "2") (pinfunction "2_2") (pintype "passive"))
      (node (ref "Q1") (pin "C") (pinfunction "C_C") (pintype "passive"))
      (node (ref "Q26") (pin "1") (pinfunction "G_1") (pintype "passive"))
      (node (ref "R2") (pin "1") (pinfunction "1_1") (pintype "passive"))
      (node (ref "R21") (pin "1") (pinfunction "1_1") (pintype "passive"))
      (node (ref "U$8") (pin "7") (pinfunction "C_7") (pintype "passive"))
    )
    (net (code "37") (name "Net-(Q26-S)") (class "Default")
      (node (ref "Q26") (pin "3") (pinfunction "S_3") (pintype "passive"))
      (node (ref "R36") (pin "1") (pinfunction "1_1") (pintype "passive"))
    )
    (net (code "38") (name "Net-(Q27-G)") (class "Default")
      (node (ref "Q27") (pin "1") (pinfunction "G_1") (pintype "passive"))
      (node (ref "R22") (pin "1") (pinfunction "1_1") (pintype "passive"))
    )
    (net (code "39") (name "Net-(Q28-G)") (class "Default")
      (node (ref "Q28") (pin "1") (pinfunction "G_1") (pintype "passive"))
      (node (ref "R30") (pin "1") (pinfunction "1_1") (pintype "passive"))
    )
    (net (code "40") (name "Net-(R45-Pad2)") (class "Default")
      (node (ref "R45") (pin "2") (pinfunction "2_2") (pintype "passive"))
      (node (ref "SJ1") (pin "1") (pinfunction "1_1") (pintype "passive"))
    )
    (net (code "41") (name "Net-(R46-Pad2)") (class "Default")
      (node (ref "R46") (pin "2") (pinfunction "2_2") (pintype "passive"))
      (node (ref "SJ2") (pin "1") (pinfunction "1_1") (pintype "passive"))
    )
    (net (code "42") (name "Net-(U$1A-D)") (class "Default")
      (node (ref "U$1") (pin "2") (pinfunction "D_2") (pintype "passive"))
      (node (ref "U$2") (pin "3") (pinfunction "E_3") (pintype "passive"))
    )
    (net (code "43") (name "Net-(U$1A-S)") (class "Default")
      (node (ref "U$1") (pin "1") (pinfunction "S_1") (pintype "passive"))
      (node (ref "VR4") (pin "3") (pinfunction "E_3") (pintype "passive"))
    )
    (net (code "44") (name "Net-(U$1B-D)") (class "Default")
      (node (ref "U$1") (pin "6") (pinfunction "D_6") (pintype "passive"))
      (node (ref "U$2") (pin "5") (pinfunction "E_5") (pintype "passive"))
    )
    (net (code "45") (name "Net-(U$1B-S)") (class "Default")
      (node (ref "U$1") (pin "5") (pinfunction "S_5") (pintype "passive"))
      (node (ref "VR4") (pin "1") (pinfunction "A_1") (pintype "passive"))
    )
    (net (code "46") (name "Net-(U$2A-B)") (class "Default")
      (node (ref "CR1") (pin "CATHODE") (pinfunction "CATHODE_CATHODE") (pintype "passive"))
      (node (ref "D1") (pin "C") (pinfunction "C_C") (pintype "passive"))
      (node (ref "U$2") (pin "2") (pinfunction "B_2") (pintype "passive"))
      (node (ref "U$2") (pin "6") (pinfunction "B_6") (pintype "passive"))
    )
    (net (code "47") (name "Net-(U$2A-C)") (class "Default")
      (node (ref "C2") (pin "2") (pinfunction "2_2") (pintype "passive"))
      (node (ref "R9") (pin "2") (pinfunction "2_2") (pintype "passive"))
      (node (ref "U$2") (pin "1") (pinfunction "C_1") (pintype "passive"))
      (node (ref "U$4") (pin "2") (pinfunction "B_2") (pintype "passive"))
    )
    (net (code "48") (name "Net-(U$2B-C)") (class "Default")
      (node (ref "C3") (pin "2") (pinfunction "2_2") (pintype "passive"))
      (node (ref "R10") (pin "2") (pinfunction "2_2") (pintype "passive"))
      (node (ref "U$2") (pin "7") (pinfunction "C_7") (pintype "passive"))
      (node (ref "U$4") (pin "6") (pinfunction "B_6") (pintype "passive"))
    )
    (net (code "49") (name "Net-(U$3A-D)") (class "Default")
      (node (ref "U$3") (pin "2") (pinfunction "D_2") (pintype "passive"))
      (node (ref "U$6") (pin "3") (pinfunction "E_3") (pintype "passive"))
    )
    (net (code "50") (name "Net-(U$3A-S)") (class "Default")
      (node (ref "D11") (pin "A") (pinfunction "A_A") (pintype "passive"))
      (node (ref "R43") (pin "1") (pinfunction "1_1") (pintype "passive"))
      (node (ref "U$3") (pin "1") (pinfunction "S_1") (pintype "passive"))
      (node (ref "U$3") (pin "5") (pinfunction "S_5") (pintype "passive"))
    )
    (net (code "51") (name "Net-(U$3B-D)") (class "Default")
      (node (ref "U$3") (pin "6") (pinfunction "D_6") (pintype "passive"))
      (node (ref "U$6") (pin "5") (pinfunction "E_5") (pintype "passive"))
    )
    (net (code "52") (name "Net-(U$4A-E)") (class "Default")
      (node (ref "R16") (pin "1") (pinfunction "1_1") (pintype "passive"))
      (node (ref "U$4") (pin "3") (pinfunction "E_3") (pintype "passive"))
    )
    (net (code "53") (name "Net-(U$4B-E)") (class "Default")
      (node (ref "R17") (pin "2") (pinfunction "2_2") (pintype "passive"))
      (node (ref "U$4") (pin "5") (pinfunction "E_5") (pintype "passive"))
    )
    (net (code "54") (name "Net-(U$5A-S)") (class "Default")
      (node (ref "R8") (pin "1") (pinfunction "1_1") (pintype "passive"))
      (node (ref "U$5") (pin "1") (pinfunction "S_1") (pintype "passive"))
    )
    (net (code "55") (name "Net-(U$5B-S)") (class "Default")
      (node (ref "R7") (pin "2") (pinfunction "2_2") (pintype "passive"))
      (node (ref "U$5") (pin "5") (pinfunction "S_5") (pintype "passive"))
    )
    (net (code "56") (name "Net-(U$6A-B)") (class "Default")
      (node (ref "CR3") (pin "CATHODE") (pinfunction "CATHODE_CATHODE") (pintype "passive"))
      (node (ref "D11") (pin "C") (pinfunction "C_C") (pintype "passive"))
      (node (ref "U$6") (pin "2") (pinfunction "B_2") (pintype "passive"))
      (node (ref "U$6") (pin "6") (pinfunction "B_6") (pintype "passive"))
    )
    (net (code "57") (name "Net-(U$6A-C)") (class "Default")
      (node (ref "C1") (pin "2") (pinfunction "2_2") (pintype "passive"))
      (node (ref "R37") (pin "2") (pinfunction "2_2") (pintype "passive"))
      (node (ref "U$6") (pin "1") (pinfunction "C_1") (pintype "passive"))
    )
    (net (code "58") (name "Net-(U$7A-C)") (class "Default")
      (node (ref "U$7") (pin "1") (pinfunction "C_1") (pintype "passive"))
      (node (ref "U$8") (pin "3") (pinfunction "E_3") (pintype "passive"))
    )
    (net (code "59") (name "Net-(U$7A-E)") (class "Default")
      (node (ref "R19") (pin "2") (pinfunction "2_2") (pintype "passive"))
      (node (ref "U$7") (pin "3") (pinfunction "E_3") (pintype "passive"))
    )
    (net (code "60") (name "Net-(U$7B-C)") (class "Default")
      (node (ref "U$7") (pin "7") (pinfunction "C_7") (pintype "passive"))
      (node (ref "U$8") (pin "5") (pinfunction "E_5") (pintype "passive"))
    )
    (net (code "61") (name "Net-(U$7B-E)") (class "Default")
      (node (ref "R18") (pin "1") (pinfunction "1_1") (pintype "passive"))
      (node (ref "U$7") (pin "5") (pinfunction "E_5") (pintype "passive"))
    )
    (net (code "62") (name "Net-(U$8A-B)") (class "Default")
      (node (ref "CR6") (pin "CATHODE") (pinfunction "CATHODE_CATHODE") (pintype "passive"))
      (node (ref "D8") (pin "C") (pinfunction "C_C") (pintype "passive"))
      (node (ref "U$8") (pin "2") (pinfunction "B_2") (pintype "passive"))
    )
    (net (code "63") (name "Net-(U$8B-B)") (class "Default")
      (node (ref "CR5") (pin "CATHODE") (pinfunction "CATHODE_CATHODE") (pintype "passive"))
      (node (ref "D7") (pin "C") (pinfunction "C_C") (pintype "passive"))
      (node (ref "U$8") (pin "6") (pinfunction "B_6") (pintype "passive"))
    )
    (net (code "64") (name "Net-(U$9A-B)") (class "Default")
      (node (ref "CR4") (pin "ANODE") (pinfunction "ANODE_ANODE") (pintype "passive"))
      (node (ref "D12") (pin "A") (pinfunction "A_A") (pintype "passive"))
      (node (ref "U$9") (pin "2") (pinfunction "B_2") (pintype "passive"))
      (node (ref "U$9") (pin "6") (pinfunction "B_6") (pintype "passive"))
    )
    (net (code "65") (name "Net-(U$9B-C)") (class "Default")
      (node (ref "C11") (pin "1") (pinfunction "1_1") (pintype "passive"))
      (node (ref "R39") (pin "1") (pinfunction "1_1") (pintype "passive"))
      (node (ref "U$9") (pin "7") (pinfunction "C_7") (pintype "passive"))
    )
    (net (code "66") (name "Net-(U$10A-B)") (class "Default")
      (node (ref "CR2") (pin "ANODE") (pinfunction "ANODE_ANODE") (pintype "passive"))
      (node (ref "D2") (pin "A") (pinfunction "A_A") (pintype "passive"))
      (node (ref "U$10") (pin "2") (pinfunction "B_2") (pintype "passive"))
      (node (ref "U$10") (pin "6") (pinfunction "B_6") (pintype "passive"))
    )
    (net (code "67") (name "Net-(U$10A-C)") (class "Default")
      (node (ref "C5") (pin "2") (pinfunction "2_2") (pintype "passive"))
      (node (ref "R12") (pin "1") (pinfunction "1_1") (pintype "passive"))
      (node (ref "U$10") (pin "1") (pinfunction "C_1") (pintype "passive"))
      (node (ref "U$7") (pin "2") (pinfunction "B_2") (pintype "passive"))
    )
    (net (code "68") (name "Net-(U$10A-E)") (class "Default")
      (node (ref "U$10") (pin "3") (pinfunction "E_3") (pintype "passive"))
      (node (ref "U$5") (pin "2") (pinfunction "D_2") (pintype "passive"))
    )
    (net (code "69") (name "Net-(U$10B-C)") (class "Default")
      (node (ref "C4") (pin "2") (pinfunction "2_2") (pintype "passive"))
      (node (ref "R11") (pin "1") (pinfunction "1_1") (pintype "passive"))
      (node (ref "U$10") (pin "7") (pinfunction "C_7") (pintype "passive"))
      (node (ref "U$7") (pin "6") (pinfunction "B_6") (pintype "passive"))
    )
    (net (code "70") (name "Net-(U$10B-E)") (class "Default")
      (node (ref "U$10") (pin "5") (pinfunction "E_5") (pintype "passive"))
      (node (ref "U$5") (pin "6") (pinfunction "D_6") (pintype "passive"))
    )
    (net (code "71") (name "Net-(U$12A-B)") (class "Default")
      (node (ref "CR5") (pin "ANODE") (pinfunction "ANODE_ANODE") (pintype "passive"))
      (node (ref "D5") (pin "A") (pinfunction "A_A") (pintype "passive"))
      (node (ref "U$12") (pin "2") (pinfunction "B_2") (pintype "passive"))
    )
    (net (code "72") (name "Net-(U$12A-E)") (class "Default")
      (node (ref "U$12") (pin "3") (pinfunction "E_3") (pintype "passive"))
      (node (ref "U$4") (pin "1") (pinfunction "C_1") (pintype "passive"))
    )
    (net (code "73") (name "Net-(U$12B-B)") (class "Default")
      (node (ref "CR6") (pin "ANODE") (pinfunction "ANODE_ANODE") (pintype "passive"))
      (node (ref "D6") (pin "A") (pinfunction "A_A") (pintype "passive"))
      (node (ref "U$12") (pin "6") (pinfunction "B_6") (pintype "passive"))
    )
    (net (code "74") (name "Net-(U$12B-E)") (class "Default")
      (node (ref "U$12") (pin "5") (pinfunction "E_5") (pintype "passive"))
      (node (ref "U$4") (pin "7") (pinfunction "C_7") (pintype "passive"))
    )
    (net (code "75") (name "Net-(U$13A-B)") (class "Default")
      (node (ref "C12") (pin "1") (pinfunction "1_1") (pintype "passive"))
      (node (ref "U$13") (pin "2") (pinfunction "B_2") (pintype "passive"))
      (node (ref "U$13") (pin "6") (pinfunction "B_6") (pintype "passive"))
      (node (ref "U$13") (pin "7") (pinfunction "C_7") (pintype "passive"))
      (node (ref "U$9") (pin "1") (pinfunction "C_1") (pintype "passive"))
    )
    (net (code "76") (name "Net-(U$13A-E)") (class "Default")
      (node (ref "R44") (pin "1") (pinfunction "1_1") (pintype "passive"))
      (node (ref "U$13") (pin "3") (pinfunction "E_3") (pintype "passive"))
    )
    (net (code "77") (name "Net-(U$13B-E)") (class "Default")
      (node (ref "R40") (pin "1") (pinfunction "1_1") (pintype "passive"))
      (node (ref "U$13") (pin "5") (pinfunction "E_5") (pintype "passive"))
    )
    (net (code "78") (name "Net-(U$14A-B)") (class "Default")
      (node (ref "C10") (pin "2") (pinfunction "2_2") (pintype "passive"))
      (node (ref "U$14") (pin "2") (pinfunction "B_2") (pintype "passive"))
      (node (ref "U$14") (pin "6") (pinfunction "B_6") (pintype "passive"))
      (node (ref "U$14") (pin "7") (pinfunction "C_7") (pintype "passive"))
      (node (ref "U$6") (pin "7") (pinfunction "C_7") (pintype "passive"))
    )
    (net (code "79") (name "Net-(U$14A-E)") (class "Default")
      (node (ref "R42") (pin "2") (pinfunction "2_2") (pintype "passive"))
      (node (ref "U$14") (pin "3") (pinfunction "E_3") (pintype "passive"))
    )
    (net (code "80") (name "Net-(U$14B-E)") (class "Default")
      (node (ref "R38") (pin "2") (pinfunction "2_2") (pintype "passive"))
      (node (ref "U$14") (pin "5") (pinfunction "E_5") (pintype "passive"))
    )
    (net (code "81") (name "Net-(U$15A-D)") (class "Default")
      (node (ref "U$15") (pin "2") (pinfunction "D_2") (pintype "passive"))
      (node (ref "U$9") (pin "3") (pinfunction "E_3") (pintype "passive"))
    )
    (net (code "82") (name "Net-(U$15A-G)") (class "Default")
      (node (ref "C10") (pin "1") (pinfunction "1_1") (pintype "passive"))
      (node (ref "C12") (pin "2") (pinfunction "2_2") (pintype "passive"))
      (node (ref "R41") (pin "1") (pinfunction "1_1") (pintype "passive"))
      (node (ref "U$15") (pin "3") (pinfunction "G_3") (pintype "passive"))
      (node (ref "U$3") (pin "7") (pinfunction "G_7") (pintype "passive"))
    )
    (net (code "83") (name "Net-(U$15A-S)") (class "Default")
      (node (ref "D12") (pin "C") (pinfunction "C_C") (pintype "passive"))
      (node (ref "R43") (pin "2") (pinfunction "2_2") (pintype "passive"))
      (node (ref "U$15") (pin "1") (pinfunction "S_1") (pintype "passive"))
      (node (ref "U$15") (pin "5") (pinfunction "S_5") (pintype "passive"))
    )
    (net (code "84") (name "Net-(U$15B-D)") (class "Default")
      (node (ref "U$15") (pin "6") (pinfunction "D_6") (pintype "passive"))
      (node (ref "U$9") (pin "5") (pinfunction "E_5") (pintype "passive"))
    )
    (net (code "85") (name "Net-(U$15B-G)") (class "Default")
      (node (ref "C1") (pin "1") (pinfunction "1_1") (pintype "passive"))
      (node (ref "C11") (pin "2") (pinfunction "2_2") (pintype "passive"))
      (node (ref "R3") (pin "2") (pinfunction "2_2") (pintype "passive"))
      (node (ref "R4") (pin "1") (pinfunction "1_1") (pintype "passive"))
      (node (ref "U$15") (pin "7") (pinfunction "G_7") (pintype "passive"))
      (node (ref "U$3") (pin "3") (pinfunction "G_3") (pintype "passive"))
    )
    (net (code "86") (name "Net-(VR1-A)") (class "Default")
      (node (ref "D1") (pin "A") (pinfunction "A_A") (pintype "passive"))
      (node (ref "VR1") (pin "1") (pinfunction "A_1") (pintype "passive"))
      (node (ref "VR1") (pin "2") (pinfunction "S_2") (pintype "passive"))
      (node (ref "VR4") (pin "2") (pinfunction "S_2") (pintype "passive"))
    )
    (net (code "87") (name "Net-(VR1-E)") (class "Default")
      (node (ref "D2") (pin "C") (pinfunction "C_C") (pintype "passive"))
      (node (ref "R7") (pin "1") (pinfunction "1_1") (pintype "passive"))
      (node (ref "R8") (pin "2") (pinfunction "2_2") (pintype "passive"))
      (node (ref "VR1") (pin "3") (pinfunction "E_3") (pintype "passive"))
    )
    (net (code "88") (name "Net-(VR2-A)") (class "Default")
      (node (ref "Q2") (pin "B") (pinfunction "B_B") (pintype "passive"))
      (node (ref "R1") (pin "1") (pinfunction "1_1") (pintype "passive"))
      (node (ref "VR2") (pin "1") (pinfunction "A_1") (pintype "passive"))
      (node (ref "VR2") (pin "2") (pinfunction "S_2") (pintype "passive"))
    )
    (net (code "89") (name "Net-(VR2-E)") (class "Default")
      (node (ref "R5") (pin "2") (pinfunction "2_2") (pintype "passive"))
      (node (ref "VR2") (pin "3") (pinfunction "E_3") (pintype "passive"))
    )
    (net (code "90") (name "Net-(VR3-A)") (class "Default")
      (node (ref "Q17") (pin "B") (pinfunction "B_B") (pintype "passive"))
      (node (ref "R25") (pin "1") (pinfunction "1_1") (pintype "passive"))
      (node (ref "VR3") (pin "1") (pinfunction "A_1") (pintype "passive"))
      (node (ref "VR3") (pin "2") (pinfunction "S_2") (pintype "passive"))
    )
    (net (code "91") (name "Net-(VR3-E)") (class "Default")
      (node (ref "R27") (pin "2") (pinfunction "2_2") (pintype "passive"))
      (node (ref "VR3") (pin "3") (pinfunction "E_3") (pintype "passive"))
    )
    (net (code "92") (name "V+") (class "Default")
      (node (ref "C17") (pin "+") (pinfunction "+_+") (pintype "passive"))
      (node (ref "D16") (pin "C") (pinfunction "C_C") (pintype "passive"))
      (node (ref "Q23") (pin "2") (pinfunction "D_2") (pintype "passive"))
      (node (ref "Q27") (pin "2") (pinfunction "D_2") (pintype "passive"))
      (node (ref "Q5") (pin "C") (pinfunction "C_C") (pintype "passive"))
    )
    (net (code "93") (name "V-") (class "Default")
      (node (ref "C18") (pin "-") (pinfunction "-_-") (pintype "passive"))
      (node (ref "D15") (pin "A") (pinfunction "A_A") (pintype "passive"))
      (node (ref "Q24") (pin "2") (pinfunction "D_2") (pintype "passive"))
      (node (ref "Q28") (pin "2") (pinfunction "D_2") (pintype "passive"))
      (node (ref "Q6") (pin "C") (pinfunction "C_C") (pintype "passive"))
    )
  )
)
